# console2.net
KiCad netlist of a schematic drawn in EAGLE
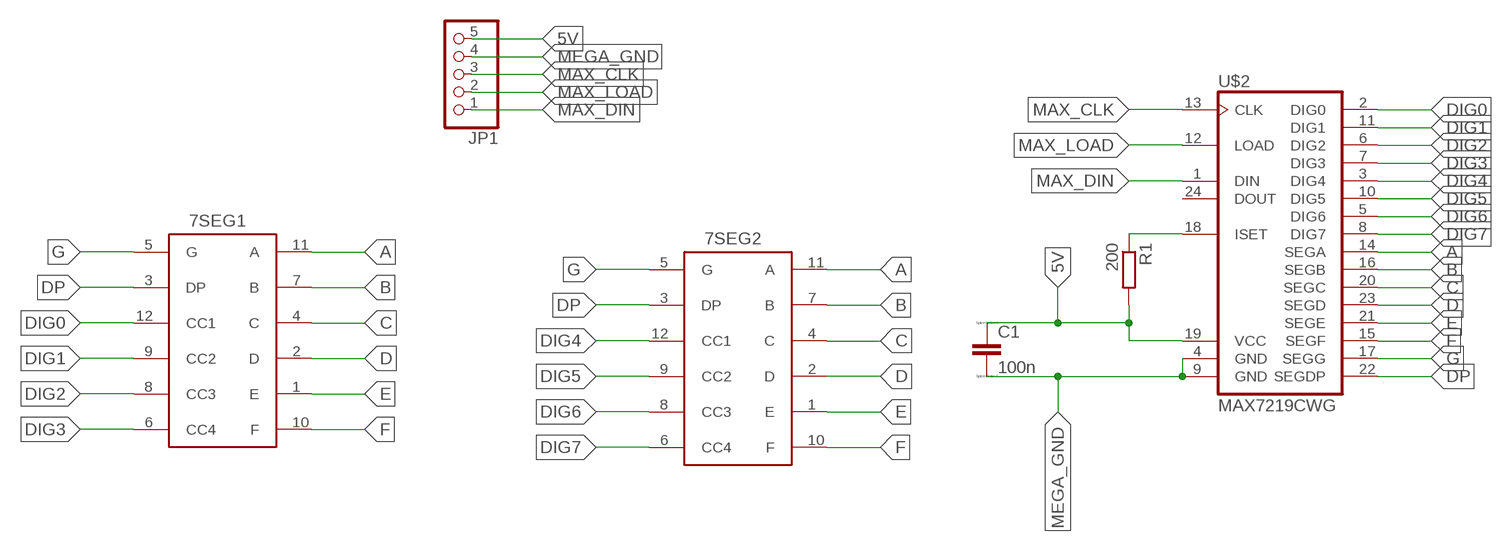
[diagram p0: schematic, sheet 1]

(export (version "E")
  (design (tool "Eeschema 10.0.6"))
  (components
    (comp (ref "7SEG1")
      (value "7SEG_DEV")
      (footprint "eagle-import:7SEG_PACK")
      (libsource (lib "eagle-import") (part "7SEG_DEV"))
    )
    (comp (ref "7SEG2")
      (value "7SEG_DEV")
      (footprint "eagle-import:7SEG_PACK")
      (libsource (lib "eagle-import") (part "7SEG_DEV"))
    )
    (comp (ref "C1")
      (value "100n")
      (footprint "eagle-import:C0805")
      (libsource (lib "eagle-import") (part "C"))
    )
    (comp (ref "JP1")
      (value "PINHD-1X5")
      (footprint "eagle-import:1X05")
      (libsource (lib "eagle-import") (part "PINHD-1X5"))
    )
    (comp (ref "R1")
      (value "200")
      (footprint "eagle-import:M3516")
      (libsource (lib "eagle-import") (part "R-EU_M3516"))
    )
    (comp (ref "U$2")
      (value "MAX7219CWG")
      (footprint "eagle-import:SO24L")
      (libsource (lib "eagle-import") (part "MAX7219CWG"))
    )
  )
  (nets
    (net (code "1") (name "5V") (class "Default")
      (node (ref "C1") (pin "1") (pinfunction "1_1") (pintype "passive"))
      (node (ref "JP1") (pin "5") (pinfunction "5_5") (pintype "passive"))
      (node (ref "R1") (pin "2") (pinfunction "2_2") (pintype "passive"))
      (node (ref "U$2") (pin "19") (pinfunction "VCC_19") (pintype "power_in"))
    )
    (net (code "2") (name "A") (class "Default")
      (node (ref "7SEG1") (pin "11") (pinfunction "A_11") (pintype "bidirectional"))
      (node (ref "7SEG2") (pin "11") (pinfunction "A_11") (pintype "bidirectional"))
      (node (ref "U$2") (pin "14") (pinfunction "SEGA_14") (pintype "output"))
    )
    (net (code "3") (name "B") (class "Default")
      (node (ref "7SEG1") (pin "7") (pinfunction "B_7") (pintype "bidirectional"))
      (node (ref "7SEG2") (pin "7") (pinfunction "B_7") (pintype "bidirectional"))
      (node (ref "U$2") (pin "16") (pinfunction "SEGB_16") (pintype "output"))
    )
    (net (code "4") (name "C") (class "Default")
      (node (ref "7SEG1") (pin "4") (pinfunction "C_4") (pintype "bidirectional"))
      (node (ref "7SEG2") (pin "4") (pinfunction "C_4") (pintype "bidirectional"))
      (node (ref "U$2") (pin "20") (pinfunction "SEGC_20") (pintype "output"))
    )
    (net (code "5") (name "D") (class "Default")
      (node (ref "7SEG1") (pin "2") (pinfunction "D_2") (pintype "bidirectional"))
      (node (ref "7SEG2") (pin "2") (pinfunction "D_2") (pintype "bidirectional"))
      (node (ref "U$2") (pin "23") (pinfunction "SEGD_23") (pintype "output"))
    )
    (net (code "6") (name "DIG0") (class "Default")
      (node (ref "7SEG1") (pin "12") (pinfunction "CC1_12") (pintype "bidirectional"))
      (node (ref "U$2") (pin "2") (pinfunction "DIG0_2") (pintype "output"))
    )
    (net (code "7") (name "DIG1") (class "Default")
      (node (ref "7SEG1") (pin "9") (pinfunction "CC2_9") (pintype "bidirectional"))
      (node (ref "U$2") (pin "11") (pinfunction "DIG1_11") (pintype "output"))
    )
    (net (code "8") (name "DIG2") (class "Default")
      (node (ref "7SEG1") (pin "8") (pinfunction "CC3_8") (pintype "bidirectional"))
      (node (ref "U$2") (pin "6") (pinfunction "DIG2_6") (pintype "output"))
    )
    (net (code "9") (name "DIG3") (class "Default")
      (node (ref "7SEG1") (pin "6") (pinfunction "CC4_6") (pintype "bidirectional"))
      (node (ref "U$2") (pin "7") (pinfunction "DIG3_7") (pintype "output"))
    )
    (net (code "10") (name "DIG4") (class "Default")
      (node (ref "7SEG2") (pin "12") (pinfunction "CC1_12") (pintype "bidirectional"))
      (node (ref "U$2") (pin "3") (pinfunction "DIG4_3") (pintype "output"))
    )
    (net (code "11") (name "DIG5") (class "Default")
      (node (ref "7SEG2") (pin "9") (pinfunction "CC2_9") (pintype "bidirectional"))
      (node (ref "U$2") (pin "10") (pinfunction "DIG5_10") (pintype "output"))
    )
    (net (code "12") (name "DIG6") (class "Default")
      (node (ref "7SEG2") (pin "8") (pinfunction "CC3_8") (pintype "bidirectional"))
      (node (ref "U$2") (pin "5") (pinfunction "DIG6_5") (pintype "output"))
    )
    (net (code "13") (name "DIG7") (class "Default")
      (node (ref "7SEG2") (pin "6") (pinfunction "CC4_6") (pintype "bidirectional"))
      (node (ref "U$2") (pin "8") (pinfunction "DIG7_8") (pintype "output"))
    )
    (net (code "14") (name "DP") (class "Default")
      (node (ref "7SEG1") (pin "3") (pinfunction "DP_3") (pintype "bidirectional"))
      (node (ref "7SEG2") (pin "3") (pinfunction "DP_3") (pintype "bidirectional"))
      (node (ref "U$2") (pin "22") (pinfunction "SEGDP_22") (pintype "output"))
    )
    (net (code "15") (name "E") (class "Default")
      (node (ref "7SEG1") (pin "1") (pinfunction "E_1") (pintype "bidirectional"))
      (node (ref "7SEG2") (pin "1") (pinfunction "E_1") (pintype "bidirectional"))
      (node (ref "U$2") (pin "21") (pinfunction "SEGE_21") (pintype "output"))
    )
    (net (code "16") (name "F") (class "Default")
      (node (ref "7SEG1") (pin "10") (pinfunction "F_10") (pintype "bidirectional"))
      (node (ref "7SEG2") (pin "10") (pinfunction "F_10") (pintype "bidirectional"))
      (node (ref "U$2") (pin "15") (pinfunction "SEGF_15") (pintype "output"))
    )
    (net (code "17") (name "G") (class "Default")
      (node (ref "7SEG1") (pin "5") (pinfunction "G_5") (pintype "bidirectional"))
      (node (ref "7SEG2") (pin "5") (pinfunction "G_5") (pintype "bidirectional"))
      (node (ref "U$2") (pin "17") (pinfunction "SEGG_17") (pintype "output"))
    )
    (net (code "18") (name "MAX_CLK") (class "Default")
      (node (ref "JP1") (pin "3") (pinfunction "3_3") (pintype "passive"))
      (node (ref "U$2") (pin "13") (pinfunction "CLK_13") (pintype "input"))
    )
    (net (code "19") (name "MAX_DIN") (class "Default")
      (node (ref "JP1") (pin "1") (pinfunction "1_1") (pintype "passive"))
      (node (ref "U$2") (pin "1") (pinfunction "DIN_1") (pintype "input"))
    )
    (net (code "20") (name "MAX_LOAD") (class "Default")
      (node (ref "JP1") (pin "2") (pinfunction "2_2") (pintype "passive"))
      (node (ref "U$2") (pin "12") (pinfunction "LOAD_12") (pintype "input"))
    )
    (net (code "21") (name "MEGA_GND") (class "Default")
      (node (ref "C1") (pin "2") (pinfunction "2_2") (pintype "passive"))
      (node (ref "JP1") (pin "4") (pinfunction "4_4") (pintype "passive"))
      (node (ref "U$2") (pin "4") (pinfunction "GND_4") (pintype "power_in"))
      (node (ref "U$2") (pin "9") (pinfunction "GND_9") (pintype "power_in"))
    )
    (net (code "22") (name "Net-(U$2-ISET)") (class "Default")
      (node (ref "R1") (pin "1") (pinfunction "1_1") (pintype "passive"))
      (node (ref "U$2") (pin "18") (pinfunction "ISET_18") (pintype "input"))
    )
    (net (code "23") (name "unconnected-(U$2-DOUT-Pad24)") (class "Default")
      (node (ref "U$2") (pin "24") (pinfunction "DOUT_24") (pintype "output"))
    )
  )
)
